# CAN_Interface.net
KiCad netlist of a schematic drawn in Altium Designer
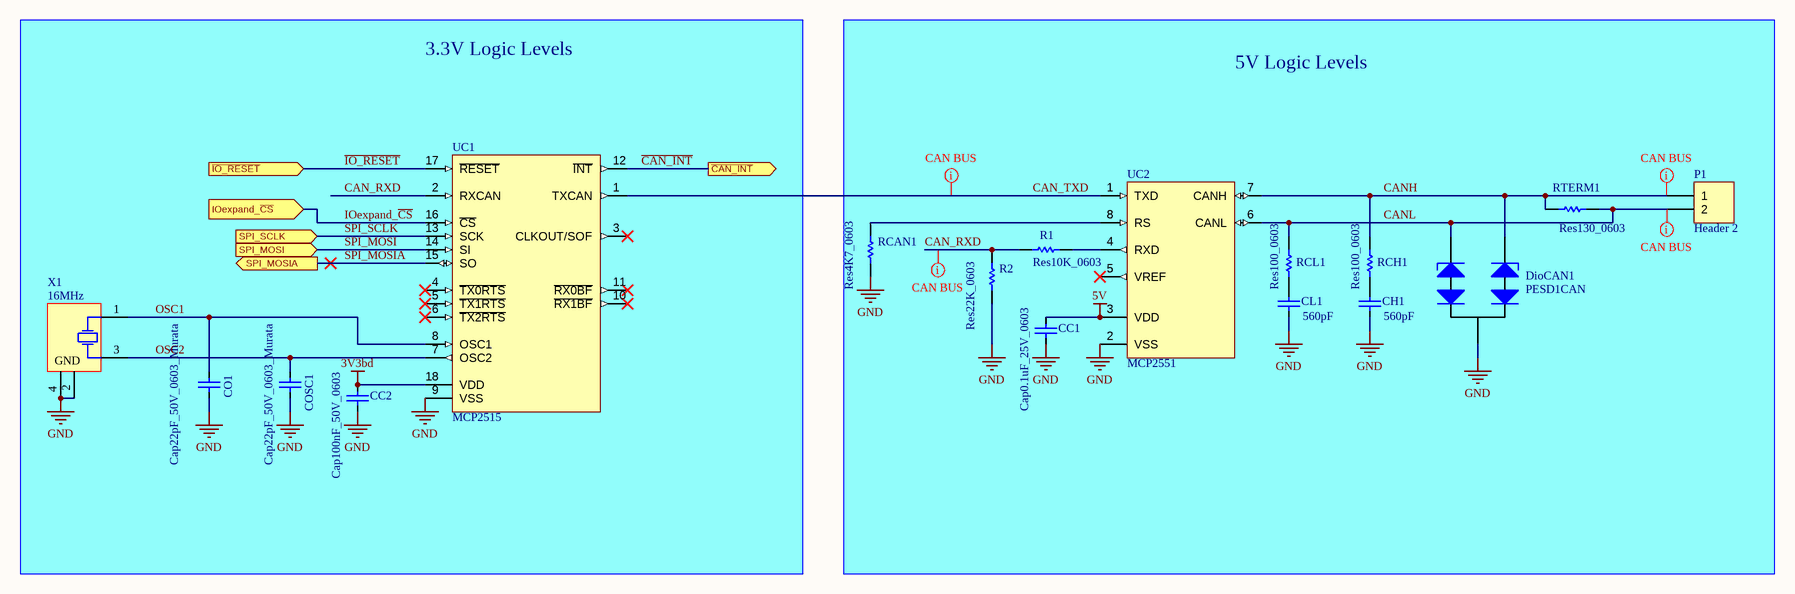
[diagram p0:  CAN_Interface.SchDoc]

(export (version "E")
  (design (tool "Eeschema 10.0.6"))
  (components
    (comp (ref "CC1")
      (value "Cap0.1uF_25V_0603")
      (footprint "0603C_L")
      (libsource (lib " Advanced] Training Course - A365") (part "CAP General"))
    )
    (comp (ref "CC2")
      (value "Cap100nF_50V_0603")
      (footprint "0603C_L")
      (libsource (lib " Advanced] Training Course - A365") (part "CAP General"))
    )
    (comp (ref "CH1")
      (value "560pF")
      (footprint "0603C_L")
      (description "560pF 25V 0603")
      (fields (field (name "Comment") "CAP General"))
      (libsource (lib " Advanced] Training Course - A365") (part "CAP General"))
    )
    (comp (ref "CL1")
      (value "560pF")
      (footprint "0603C_L")
      (description "560pF 25V 0603")
      (fields (field (name "Comment") "CAP General"))
      (libsource (lib " Advanced] Training Course - A365") (part "CAP General"))
    )
    (comp (ref "CO1")
      (value "Cap22pF_50V_0603_Murata")
      (footprint "0603C_L")
      (fields (field (name "TOLERANCE") "5%"))
      (libsource (lib " Advanced] Training Course - A365") (part "CAP General"))
    )
    (comp (ref "COSC1")
      (value "Cap22pF_50V_0603_Murata")
      (footprint "0603C_L")
      (fields (field (name "TOLERANCE") "5%"))
      (libsource (lib " Advanced] Training Course - A365") (part "CAP General"))
    )
    (comp (ref "DioCAN1")
      (value "PESD1CAN")
      (footprint "SOT323")
      (description "Trans Voltage Suppressor Diode, 150W, 24V V(RWM), Bidirectional, 2 Element, Silicon")
      (fields (field (name "MANUFACTURER") "Nexperia USA Inc.") (field (name "SOURCE") "WCT.SchLib"))
      (libsource (lib " Advanced] Training Course - A365") (part "PESD1CAN"))
    )
    (comp (ref "P1")
      (value "Header 2")
      (footprint "HDR1X2")
      (description "Header, 2-Pin")
      (fields (field (name "PUBLISHER") "Altium Limited") (field (name "SOURCE") "WCT.SchLib"))
      (libsource (lib " Advanced] Training Course - A365") (part "Header 2"))
    )
    (comp (ref "R1")
      (value "Res10K_0603")
      (footprint "0603_L")
      (fields
        (field (name "MANUFACTURER") "Panasonic Electronic Components")
        (field (name "MANUFACTURER PART NUMBER") "ERJ-3GEYJ102V")
        (field (name "TOLERANCE") "5%")
        (field (name "SOURCE") "WCT.SchLib")
      )
      (libsource (lib " Advanced] Training Course - A365") (part "Resistor General"))
    )
    (comp (ref "R2")
      (value "Res22K_0603")
      (footprint "0603_L")
      (description "RES22K 0.5% 0603")
      (fields
        (field (name "MANUFACTURER") "Yageo")
        (field (name "MANUFACTURER PART NUMBER") "RT0603DRD0722KL")
        (field (name "SOURCE") "WCT.SchLib")
      )
      (libsource (lib " Advanced] Training Course - A365") (part "Resistor General"))
    )
    (comp (ref "RCAN1")
      (value "Res4K7_0603")
      (footprint "0603_L")
      (fields
        (field (name "MANUFACTURER") "Yageo")
        (field (name "TOLERANCE") "0.5%")
        (field (name "SOURCE") "WCT.SchLib")
      )
      (libsource (lib " Advanced] Training Course - A365") (part "Resistor General"))
    )
    (comp (ref "RCH1")
      (value "Res100_0603")
      (footprint "0603_L")
      (fields
        (field (name "MANUFACTURER") "Panasonic Electronic Components")
        (field (name "TOLERANCE") "5%")
        (field (name "SOURCE") "WCT.SchLib")
      )
      (libsource (lib " Advanced] Training Course - A365") (part "Resistor General"))
    )
    (comp (ref "RCL1")
      (value "Res100_0603")
      (footprint "0603_L")
      (fields
        (field (name "MANUFACTURER") "Panasonic Electronic Components")
        (field (name "TOLERANCE") "5%")
        (field (name "SOURCE") "WCT.SchLib")
      )
      (libsource (lib " Advanced] Training Course - A365") (part "Resistor General"))
    )
    (comp (ref "RTERM1")
      (value "Res130_0603")
      (footprint "0603_L")
      (fields
        (field (name "MANUFACTURER") "Panasonic Electronic Components")
        (field (name "TOLERANCE") "5%")
        (field (name "SOURCE") "WCT.SchLib")
      )
      (libsource (lib " Advanced] Training Course - A365") (part "Resistor General"))
    )
    (comp (ref "UC1")
      (value "MCP2515")
      (footprint "SOIC-SO18_M")
      (description "Stand-Alone CAN Controller With SPI Interface, 18-Pin SOIC, Extended Temperature")
      (fields
        (field (name "MANUFACTURER") "Microchip")
        (field (name "MANUFACTURER PART NUMBER") "MCP2515-E/SO")
        (field (name "AVAILABLE PREVIEW IMAGES") "2D")
        (field (name "SOURCE") "WCT.SchLib")
      )
      (libsource (lib " Advanced] Training Course - A365") (part "MCP2515"))
    )
    (comp (ref "UC2")
      (value "MCP2551")
      (footprint "SOIC-SN8_N")
      (description "High-Speed CAN Transceiver, 8-Pin SOIC, Extended Temperature")
      (fields
        (field (name "MANUFACTURER") "Microchip")
        (field (name "MANUFACTURER PART NUMBER") "MCP2551-E/SN")
        (field (name "AVAILABLE PREVIEW IMAGES") "2D")
        (field (name "SOURCE") "WCT.SchLib")
      )
      (libsource (lib " Advanced] Training Course - A365") (part "MCP2551"))
    )
    (comp (ref "X1")
      (value "Crystal 4Pin")
      (footprint "FP-ABM8-MFG")
      (description "Crystal 16MHz ±20ppm 18pF SMD-4 3.2mm x 2.5mm CSTCE16M0V53-R0 ABM8-16.000MHZ-B2-T")
      (fields
        (field (name "TOLERANCE") "20ppm")
        (field (name "FREQUENCY") "16MHz")
        (field (name "SOURCE") "WCT.SchLib")
      )
      (libsource (lib " Advanced] Training Course - A365") (part "Crystal 4Pin"))
    )
  )
  (nets
    (net (code "1") (name "/CANH") (class "Default")
      (node (ref "DioCAN1") (pin "1") (pinfunction "A_1") (pintype "passive"))
      (node (ref "P1") (pin "1") (pinfunction "1_1") (pintype "passive"))
      (node (ref "RCH1") (pin "2") (pinfunction "2_2") (pintype "passive"))
      (node (ref "RTERM1") (pin "2") (pinfunction "2_2") (pintype "passive"))
      (node (ref "UC2") (pin "7") (pinfunction "CANH_7") (pintype "bidirectional"))
    )
    (net (code "2") (name "/CANL") (class "Default")
      (node (ref "DioCAN1") (pin "2") (pinfunction "K_2") (pintype "passive"))
      (node (ref "P1") (pin "2") (pinfunction "2_2") (pintype "passive"))
      (node (ref "RCL1") (pin "2") (pinfunction "2_2") (pintype "passive"))
      (node (ref "RTERM1") (pin "1") (pinfunction "1_1") (pintype "passive"))
      (node (ref "UC2") (pin "6") (pinfunction "CANL_6") (pintype "bidirectional"))
    )
    (net (code "3") (name "/CAN_INT") (class "Default")
      (node (ref "UC1") (pin "12") (pinfunction "~{INT}_12") (pintype "output"))
    )
    (net (code "4") (name "/CAN_RXD") (class "Default")
      (node (ref "R1") (pin "2") (pinfunction "2_2") (pintype "passive"))
      (node (ref "R2") (pin "2") (pinfunction "2_2") (pintype "passive"))
      (node (ref "UC1") (pin "2") (pinfunction "RXCAN_2") (pintype "input"))
    )
    (net (code "5") (name "/CAN_TXD") (class "Default")
      (node (ref "UC1") (pin "1") (pinfunction "TXCAN_1") (pintype "output"))
      (node (ref "UC2") (pin "1") (pinfunction "TXD_1") (pintype "input"))
    )
    (net (code "6") (name "/IO_RESET") (class "Default")
      (node (ref "UC1") (pin "17") (pinfunction "~{RESET}_17") (pintype "input"))
    )
    (net (code "7") (name "/IOexpand_~{CS}") (class "Default")
      (node (ref "UC1") (pin "16") (pinfunction "~{CS}_16") (pintype "input"))
    )
    (net (code "8") (name "/OSC1") (class "Default")
      (node (ref "CO1") (pin "2") (pinfunction "2_2") (pintype "passive"))
      (node (ref "UC1") (pin "8") (pinfunction "OSC1_8") (pintype "input"))
      (node (ref "X1") (pin "1") (pinfunction "1_1") (pintype "passive"))
    )
    (net (code "9") (name "/OSC2") (class "Default")
      (node (ref "COSC1") (pin "2") (pinfunction "2_2") (pintype "passive"))
      (node (ref "UC1") (pin "7") (pinfunction "OSC2_7") (pintype "output"))
      (node (ref "X1") (pin "3") (pinfunction "3_3") (pintype "passive"))
    )
    (net (code "10") (name "/SPI_MOSI") (class "Default")
      (node (ref "UC1") (pin "14") (pinfunction "SI_14") (pintype "input"))
    )
    (net (code "11") (name "/SPI_MOSIA") (class "Default")
      (node (ref "UC1") (pin "15") (pinfunction "SO_15") (pintype "bidirectional"))
    )
    (net (code "12") (name "/SPI_SCLK") (class "Default")
      (node (ref "UC1") (pin "13") (pinfunction "SCK_13") (pintype "input"))
    )
    (net (code "13") (name "3V3bd") (class "Default")
      (node (ref "CC2") (pin "2") (pinfunction "2_2") (pintype "passive"))
      (node (ref "UC1") (pin "18") (pinfunction "VDD_18") (pintype "power_in"))
    )
    (net (code "14") (name "5V") (class "Default")
      (node (ref "CC1") (pin "2") (pinfunction "2_2") (pintype "passive"))
      (node (ref "UC2") (pin "3") (pinfunction "VDD_3") (pintype "power_in"))
    )
    (net (code "15") (name "GND") (class "Default")
      (node (ref "CC1") (pin "1") (pinfunction "1_1") (pintype "passive"))
      (node (ref "CC2") (pin "1") (pinfunction "1_1") (pintype "passive"))
      (node (ref "CH1") (pin "2") (pinfunction "2_2") (pintype "passive"))
      (node (ref "CL1") (pin "1") (pinfunction "1_1") (pintype "passive"))
      (node (ref "CO1") (pin "1") (pinfunction "1_1") (pintype "passive"))
      (node (ref "COSC1") (pin "1") (pinfunction "1_1") (pintype "passive"))
      (node (ref "DioCAN1") (pin "3") (pinfunction "3_3") (pintype "passive"))
      (node (ref "R2") (pin "1") (pinfunction "1_1") (pintype "passive"))
      (node (ref "RCAN1") (pin "1") (pinfunction "1_1") (pintype "passive"))
      (node (ref "UC1") (pin "9") (pinfunction "VSS_9") (pintype "power_in"))
      (node (ref "UC2") (pin "2") (pinfunction "VSS_2") (pintype "power_in"))
      (node (ref "X1") (pin "2") (pinfunction "GND_2") (pintype "power_in"))
      (node (ref "X1") (pin "4") (pinfunction "GND_4") (pintype "power_in"))
    )
    (net (code "16") (name "Net-(CH1-Pad1)") (class "Default")
      (node (ref "CH1") (pin "1") (pinfunction "1_1") (pintype "passive"))
      (node (ref "RCH1") (pin "1") (pinfunction "1_1") (pintype "passive"))
    )
    (net (code "17") (name "Net-(CL1-Pad2)") (class "Default")
      (node (ref "CL1") (pin "2") (pinfunction "2_2") (pintype "passive"))
      (node (ref "RCL1") (pin "1") (pinfunction "1_1") (pintype "passive"))
    )
    (net (code "18") (name "Net-(UC2-RS)") (class "Default")
      (node (ref "RCAN1") (pin "2") (pinfunction "2_2") (pintype "passive"))
      (node (ref "UC2") (pin "8") (pinfunction "RS_8") (pintype "input"))
    )
    (net (code "19") (name "Net-(UC2-RXD)") (class "Default")
      (node (ref "R1") (pin "1") (pinfunction "1_1") (pintype "passive"))
      (node (ref "UC2") (pin "4") (pinfunction "RXD_4") (pintype "output"))
    )
    (net (code "20") (name "unconnected-(UC1-CLKOUT{slash}SOF-Pad3)") (class "Default")
      (node (ref "UC1") (pin "3") (pinfunction "CLKOUT/SOF_3") (pintype "output+no_connect"))
    )
    (net (code "21") (name "unconnected-(UC1-~{RX0BF}-Pad11)") (class "Default")
      (node (ref "UC1") (pin "11") (pinfunction "~{RX0BF}_11") (pintype "output+no_connect"))
    )
    (net (code "22") (name "unconnected-(UC1-~{RX1BF}-Pad10)") (class "Default")
      (node (ref "UC1") (pin "10") (pinfunction "~{RX1BF}_10") (pintype "output+no_connect"))
    )
    (net (code "23") (name "unconnected-(UC1-~{TX0RTS}-Pad4)") (class "Default")
      (node (ref "UC1") (pin "4") (pinfunction "~{TX0RTS}_4") (pintype "input+no_connect"))
    )
    (net (code "24") (name "unconnected-(UC1-~{TX1RTS}-Pad5)") (class "Default")
      (node (ref "UC1") (pin "5") (pinfunction "~{TX1RTS}_5") (pintype "input+no_connect"))
    )
    (net (code "25") (name "unconnected-(UC1-~{TX2RTS}-Pad6)") (class "Default")
      (node (ref "UC1") (pin "6") (pinfunction "~{TX2RTS}_6") (pintype "input+no_connect"))
    )
    (net (code "26") (name "unconnected-(UC2-VREF-Pad5)") (class "Default")
      (node (ref "UC2") (pin "5") (pinfunction "VREF_5") (pintype "output+no_connect"))
    )
  )
)
